# SPv0.net
KiCad netlist of a schematic drawn in EAGLE
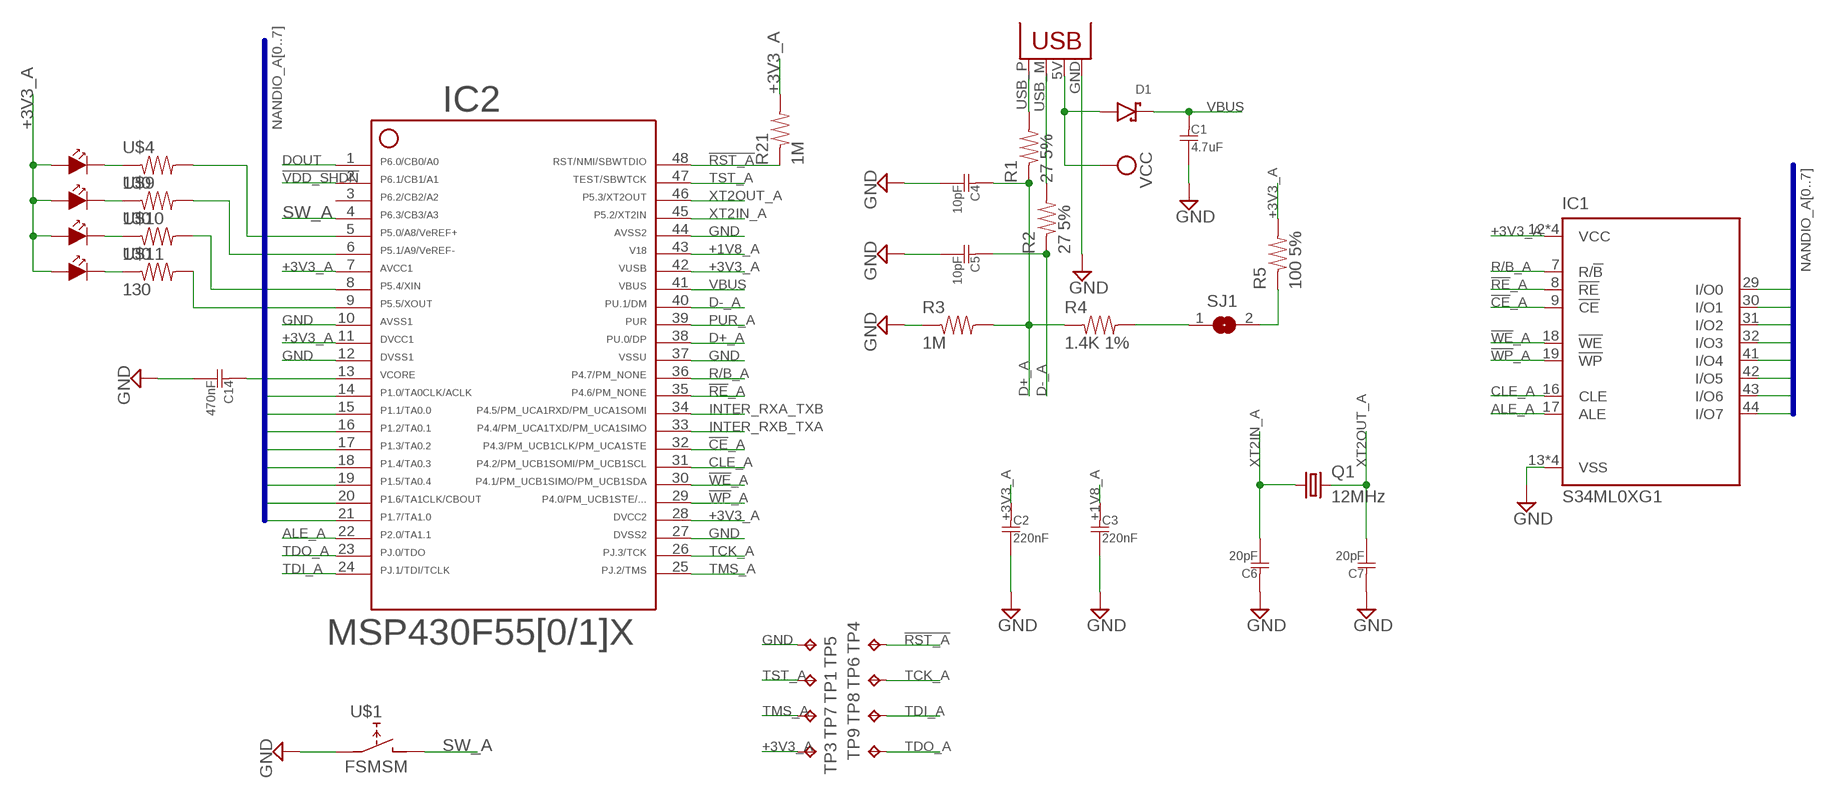
[diagram p0: schematic, sheet 1]
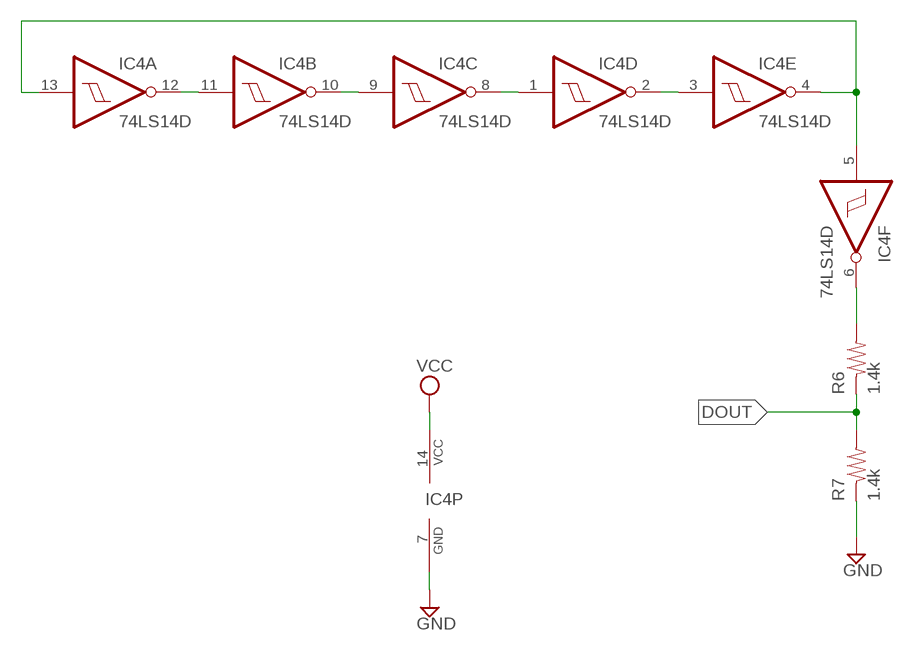
[diagram p1: schematic, sheet 2]

(export (version "E")
  (design (tool "Eeschema 10.0.6"))
  (components
    (comp (ref "IC4")
      (value "74LS14D")
      (footprint "eagle-import:SO14")
      (libsource (lib "eagle-import") (part "7414DLS"))
    )
    (comp (ref "R6")
      (value "1.4k")
      (footprint "eagle-import:R0805")
      (libsource (lib "eagle-import") (part "R0805"))
    )
    (comp (ref "R7")
      (value "1.4k")
      (footprint "eagle-import:R0805")
      (libsource (lib "eagle-import") (part "R0805"))
    )
    (comp (ref "C1")
      (value "4.7uF")
      (footprint "eagle-import:R0805")
      (libsource (lib "eagle-import") (part "C0805"))
    )
    (comp (ref "C2")
      (value "220nF")
      (footprint "eagle-import:R0805")
      (libsource (lib "eagle-import") (part "C0805"))
    )
    (comp (ref "C3")
      (value "220nF")
      (footprint "eagle-import:R0805")
      (libsource (lib "eagle-import") (part "C0805"))
    )
    (comp (ref "C4")
      (value "10pF")
      (footprint "eagle-import:R0805")
      (libsource (lib "eagle-import") (part "C0805"))
    )
    (comp (ref "C5")
      (value "10pF")
      (footprint "eagle-import:R0805")
      (libsource (lib "eagle-import") (part "C0805"))
    )
    (comp (ref "C6")
      (value "20pF")
      (footprint "eagle-import:R0805")
      (libsource (lib "eagle-import") (part "C0805"))
    )
    (comp (ref "C7")
      (value "20pF")
      (footprint "eagle-import:R0805")
      (libsource (lib "eagle-import") (part "C0805"))
    )
    (comp (ref "C14")
      (value "470nF")
      (footprint "eagle-import:R0805")
      (libsource (lib "eagle-import") (part "C0805"))
    )
    (comp (ref "D1")
      (value "D-SCHOTTKY")
      (footprint "eagle-import:SOD123")
      (libsource (lib "eagle-import") (part "D-SCHOTTKY"))
    )
    (comp (ref "IC1")
      (value "S34ML0XG1")
      (footprint "eagle-import:TSOP48")
      (libsource (lib "eagle-import") (part "S34ML0XG1"))
    )
    (comp (ref "IC2")
      (value "F55[0/1]X---PT48")
      (footprint "eagle-import:PT48")
      (libsource (lib "eagle-import") (part "F55[0/1]X---PT48"))
    )
    (comp (ref "JP1")
      (value "USBPCB")
      (footprint "eagle-import:USB-A-PCB")
      (libsource (lib "eagle-import") (part "USBPCB"))
    )
    (comp (ref "Q1")
      (value "12MHz")
      (footprint "eagle-import:CSM-3X")
      (libsource (lib "eagle-import") (part "CRYSTALCSM-3X"))
    )
    (comp (ref "R1")
      (value "27 5%")
      (footprint "eagle-import:R0805")
      (libsource (lib "eagle-import") (part "R0805"))
    )
    (comp (ref "R2")
      (value "27 5%")
      (footprint "eagle-import:R0805")
      (libsource (lib "eagle-import") (part "R0805"))
    )
    (comp (ref "R3")
      (value "1M")
      (footprint "eagle-import:R0805")
      (libsource (lib "eagle-import") (part "R0805"))
    )
    (comp (ref "R4")
      (value "1.4K 1%")
      (footprint "eagle-import:R0805")
      (libsource (lib "eagle-import") (part "R0805"))
    )
    (comp (ref "R5")
      (value "100 5%")
      (footprint "eagle-import:R0805")
      (libsource (lib "eagle-import") (part "R0805"))
    )
    (comp (ref "R21")
      (value "1M")
      (footprint "eagle-import:R0805")
      (libsource (lib "eagle-import") (part "R0805"))
    )
    (comp (ref "SJ1")
      (value "SJW")
      (footprint "eagle-import:SJW")
      (libsource (lib "eagle-import") (part "SJW"))
    )
    (comp (ref "TP1")
      (value "TPTP08SQ")
      (footprint "eagle-import:TP08SQ")
      (libsource (lib "eagle-import") (part "TPTP08SQ"))
    )
    (comp (ref "TP3")
      (value "TPTP08SQ")
      (footprint "eagle-import:TP08SQ")
      (libsource (lib "eagle-import") (part "TPTP08SQ"))
    )
    (comp (ref "TP4")
      (value "TPTP08SQ")
      (footprint "eagle-import:TP08SQ")
      (libsource (lib "eagle-import") (part "TPTP08SQ"))
    )
    (comp (ref "TP5")
      (value "TPTP08SQ")
      (footprint "eagle-import:TP08SQ")
      (libsource (lib "eagle-import") (part "TPTP08SQ"))
    )
    (comp (ref "TP6")
      (value "TPTP08SQ")
      (footprint "eagle-import:TP08SQ")
      (libsource (lib "eagle-import") (part "TPTP08SQ"))
    )
    (comp (ref "TP7")
      (value "TPTP08SQ")
      (footprint "eagle-import:TP08SQ")
      (libsource (lib "eagle-import") (part "TPTP08SQ"))
    )
    (comp (ref "TP8")
      (value "TPTP08SQ")
      (footprint "eagle-import:TP08SQ")
      (libsource (lib "eagle-import") (part "TPTP08SQ"))
    )
    (comp (ref "TP9")
      (value "TPTP08SQ")
      (footprint "eagle-import:TP08SQ")
      (libsource (lib "eagle-import") (part "TPTP08SQ"))
    )
    (comp (ref "U$1")
      (value "FSMSM")
      (footprint "eagle-import:FSMSM")
      (libsource (lib "eagle-import") (part "FSMSM"))
    )
    (comp (ref "U$4")
      (value "130")
      (footprint "eagle-import:R0805")
      (libsource (lib "eagle-import") (part "R0805"))
    )
    (comp (ref "U$5")
      (value "LED")
      (footprint "eagle-import:LED0805")
      (libsource (lib "eagle-import") (part "LED"))
    )
    (comp (ref "U$6")
      (value "LED")
      (footprint "eagle-import:LED0805")
      (libsource (lib "eagle-import") (part "LED"))
    )
    (comp (ref "U$7")
      (value "LED")
      (footprint "eagle-import:LED0805")
      (libsource (lib "eagle-import") (part "LED"))
    )
    (comp (ref "U$8")
      (value "LED")
      (footprint "eagle-import:LED0805")
      (libsource (lib "eagle-import") (part "LED"))
    )
    (comp (ref "U$9")
      (value "130")
      (footprint "eagle-import:R0805")
      (libsource (lib "eagle-import") (part "R0805"))
    )
    (comp (ref "U$10")
      (value "130")
      (footprint "eagle-import:R0805")
      (libsource (lib "eagle-import") (part "R0805"))
    )
    (comp (ref "U$11")
      (value "130")
      (footprint "eagle-import:R0805")
      (libsource (lib "eagle-import") (part "R0805"))
    )
  )
  (nets
    (net (code "1") (name "+1V8_A") (class "Default")
      (node (ref "C3") (pin "P$1") (pinfunction "1_P$1") (pintype "passive"))
      (node (ref "IC2") (pin "43") (pinfunction "43_43") (pintype "power_in"))
    )
    (net (code "2") (name "+3V3_A") (class "Default")
      (node (ref "C2") (pin "P$1") (pinfunction "1_P$1") (pintype "passive"))
      (node (ref "IC1") (pin "12") (pinfunction "VCC_12") (pintype "power_in"))
      (node (ref "IC1") (pin "34") (pinfunction "VCC_34") (pintype "power_in"))
      (node (ref "IC1") (pin "37") (pinfunction "VCC_37") (pintype "power_in"))
      (node (ref "IC1") (pin "39") (pinfunction "VCC_39") (pintype "power_in"))
      (node (ref "IC2") (pin "11") (pinfunction "11_11") (pintype "power_in"))
      (node (ref "IC2") (pin "28") (pinfunction "28_28") (pintype "power_in"))
      (node (ref "IC2") (pin "42") (pinfunction "42_42") (pintype "power_in"))
      (node (ref "IC2") (pin "7") (pinfunction "7_7") (pintype "power_in"))
      (node (ref "R21") (pin "P$2") (pinfunction "2_P$2") (pintype "passive"))
      (node (ref "R5") (pin "P$2") (pinfunction "2_P$2") (pintype "passive"))
      (node (ref "TP3") (pin "TP") (pinfunction "TP_TP") (pintype "input"))
      (node (ref "U$5") (pin "ANODE") (pinfunction "ANODE_ANODE") (pintype "passive"))
      (node (ref "U$6") (pin "ANODE") (pinfunction "ANODE_ANODE") (pintype "passive"))
      (node (ref "U$7") (pin "ANODE") (pinfunction "ANODE_ANODE") (pintype "passive"))
      (node (ref "U$8") (pin "ANODE") (pinfunction "ANODE_ANODE") (pintype "passive"))
    )
    (net (code "4") (name "ALE_A") (class "Default")
      (node (ref "IC1") (pin "17") (pinfunction "ALE_17") (pintype "input"))
      (node (ref "IC2") (pin "22") (pinfunction "22_22") (pintype "bidirectional"))
    )
    (net (code "5") (name "CLE_A") (class "Default")
      (node (ref "IC1") (pin "16") (pinfunction "CLE_16") (pintype "input"))
      (node (ref "IC2") (pin "31") (pinfunction "31_31") (pintype "bidirectional"))
    )
    (net (code "6") (name "D+_A") (class "Default")
      (node (ref "C4") (pin "P$1") (pinfunction "1_P$1") (pintype "passive"))
      (node (ref "IC2") (pin "38") (pinfunction "38_38") (pintype "bidirectional"))
      (node (ref "R1") (pin "P$1") (pinfunction "1_P$1") (pintype "passive"))
      (node (ref "R3") (pin "P$2") (pinfunction "2_P$2") (pintype "passive"))
      (node (ref "R4") (pin "P$1") (pinfunction "1_P$1") (pintype "passive"))
    )
    (net (code "7") (name "D-_A") (class "Default")
      (node (ref "C5") (pin "P$1") (pinfunction "1_P$1") (pintype "passive"))
      (node (ref "IC2") (pin "40") (pinfunction "40_40") (pintype "bidirectional"))
      (node (ref "R2") (pin "P$1") (pinfunction "1_P$1") (pintype "passive"))
    )
    (net (code "8") (name "DOUT") (class "Default")
      (node (ref "IC2") (pin "1") (pinfunction "1_1") (pintype "bidirectional"))
      (node (ref "R6") (pin "P$1") (pinfunction "1_P$1") (pintype "passive"))
      (node (ref "R7") (pin "P$2") (pinfunction "2_P$2") (pintype "passive"))
    )
    (net (code "9") (name "GND") (class "Default")
      (node (ref "C1") (pin "P$2") (pinfunction "2_P$2") (pintype "passive"))
      (node (ref "C14") (pin "P$2") (pinfunction "2_P$2") (pintype "passive"))
      (node (ref "C2") (pin "P$2") (pinfunction "2_P$2") (pintype "passive"))
      (node (ref "C3") (pin "P$2") (pinfunction "2_P$2") (pintype "passive"))
      (node (ref "C4") (pin "P$2") (pinfunction "2_P$2") (pintype "passive"))
      (node (ref "C5") (pin "P$2") (pinfunction "2_P$2") (pintype "passive"))
      (node (ref "C6") (pin "P$1") (pinfunction "1_P$1") (pintype "passive"))
      (node (ref "C7") (pin "P$1") (pinfunction "1_P$1") (pintype "passive"))
      (node (ref "IC1") (pin "13") (pinfunction "VSS_13") (pintype "power_in"))
      (node (ref "IC1") (pin "25") (pinfunction "VSS_25") (pintype "power_in"))
      (node (ref "IC1") (pin "36") (pinfunction "VSS_36") (pintype "power_in"))
      (node (ref "IC1") (pin "48") (pinfunction "VSS_48") (pintype "power_in"))
      (node (ref "IC2") (pin "10") (pinfunction "10_10") (pintype "power_in"))
      (node (ref "IC2") (pin "12") (pinfunction "12_12") (pintype "power_in"))
      (node (ref "IC2") (pin "27") (pinfunction "27_27") (pintype "power_in"))
      (node (ref "IC2") (pin "37") (pinfunction "37_37") (pintype "power_in"))
      (node (ref "IC2") (pin "44") (pinfunction "44_44") (pintype "power_in"))
      (node (ref "IC4") (pin "7") (pinfunction "GND_7") (pintype "power_in"))
      (node (ref "JP1") (pin "GND") (pinfunction "GND_GND") (pintype "bidirectional"))
      (node (ref "R3") (pin "P$1") (pinfunction "1_P$1") (pintype "passive"))
      (node (ref "R7") (pin "P$1") (pinfunction "1_P$1") (pintype "passive"))
      (node (ref "TP5") (pin "TP") (pinfunction "TP_TP") (pintype "input"))
      (node (ref "U$1") (pin "P$1") (pinfunction "A1_P$1") (pintype "passive"))
    )
    (net (code "10") (name "INTER_RXA_TXB") (class "Default")
      (node (ref "IC2") (pin "34") (pinfunction "34_34") (pintype "bidirectional"))
    )
    (net (code "11") (name "INTER_RXB_TXA") (class "Default")
      (node (ref "IC2") (pin "33") (pinfunction "33_33") (pintype "bidirectional"))
    )
    (net (code "12") (name "NANDIO_A0") (class "Default")
      (node (ref "IC1") (pin "29") (pinfunction "I/O0_29") (pintype "bidirectional"))
      (node (ref "IC2") (pin "14") (pinfunction "14_14") (pintype "bidirectional"))
    )
    (net (code "13") (name "NANDIO_A1") (class "Default")
      (node (ref "IC1") (pin "30") (pinfunction "I/O1_30") (pintype "bidirectional"))
      (node (ref "IC2") (pin "15") (pinfunction "15_15") (pintype "bidirectional"))
    )
    (net (code "14") (name "NANDIO_A2") (class "Default")
      (node (ref "IC1") (pin "31") (pinfunction "I/O2_31") (pintype "bidirectional"))
      (node (ref "IC2") (pin "16") (pinfunction "16_16") (pintype "bidirectional"))
    )
    (net (code "15") (name "NANDIO_A3") (class "Default")
      (node (ref "IC1") (pin "32") (pinfunction "I/O3_32") (pintype "bidirectional"))
      (node (ref "IC2") (pin "17") (pinfunction "17_17") (pintype "bidirectional"))
    )
    (net (code "16") (name "NANDIO_A4") (class "Default")
      (node (ref "IC1") (pin "41") (pinfunction "I/O4_41") (pintype "bidirectional"))
      (node (ref "IC2") (pin "18") (pinfunction "18_18") (pintype "bidirectional"))
    )
    (net (code "17") (name "NANDIO_A5") (class "Default")
      (node (ref "IC1") (pin "42") (pinfunction "I/O5_42") (pintype "bidirectional"))
      (node (ref "IC2") (pin "19") (pinfunction "19_19") (pintype "bidirectional"))
    )
    (net (code "18") (name "NANDIO_A6") (class "Default")
      (node (ref "IC1") (pin "43") (pinfunction "I/O6_43") (pintype "bidirectional"))
      (node (ref "IC2") (pin "20") (pinfunction "20_20") (pintype "bidirectional"))
    )
    (net (code "19") (name "NANDIO_A7") (class "Default")
      (node (ref "IC1") (pin "44") (pinfunction "I/O7_44") (pintype "bidirectional"))
      (node (ref "IC2") (pin "21") (pinfunction "21_21") (pintype "bidirectional"))
    )
    (net (code "20") (name "Net-(C14-1)") (class "Default")
      (node (ref "C14") (pin "P$1") (pinfunction "1_P$1") (pintype "passive"))
      (node (ref "IC2") (pin "13") (pinfunction "13_13") (pintype "power_in"))
    )
    (net (code "21") (name "Net-(IC4A-I)") (class "Default")
      (node (ref "IC4") (pin "13") (pinfunction "I_13") (pintype "input"))
      (node (ref "IC4") (pin "4") (pinfunction "O_4") (pintype "output"))
      (node (ref "IC4") (pin "5") (pinfunction "I_5") (pintype "input"))
    )
    (net (code "22") (name "Net-(IC4A-O)") (class "Default")
      (node (ref "IC4") (pin "11") (pinfunction "I_11") (pintype "input"))
      (node (ref "IC4") (pin "12") (pinfunction "O_12") (pintype "output"))
    )
    (net (code "23") (name "Net-(IC4B-O)") (class "Default")
      (node (ref "IC4") (pin "10") (pinfunction "O_10") (pintype "output"))
      (node (ref "IC4") (pin "9") (pinfunction "I_9") (pintype "input"))
    )
    (net (code "24") (name "Net-(IC4C-O)") (class "Default")
      (node (ref "IC4") (pin "1") (pinfunction "I_1") (pintype "input"))
      (node (ref "IC4") (pin "8") (pinfunction "O_8") (pintype "output"))
    )
    (net (code "25") (name "Net-(IC4D-O)") (class "Default")
      (node (ref "IC4") (pin "2") (pinfunction "O_2") (pintype "output"))
      (node (ref "IC4") (pin "3") (pinfunction "I_3") (pintype "input"))
    )
    (net (code "26") (name "Net-(IC4F-O)") (class "Default")
      (node (ref "IC4") (pin "6") (pinfunction "O_6") (pintype "output"))
      (node (ref "R6") (pin "P$2") (pinfunction "2_P$2") (pintype "passive"))
    )
    (net (code "27") (name "Net-(JP1-D+)") (class "Default")
      (node (ref "JP1") (pin "USB_P") (pinfunction "D+_USB_P") (pintype "bidirectional"))
      (node (ref "R1") (pin "P$2") (pinfunction "2_P$2") (pintype "passive"))
    )
    (net (code "28") (name "Net-(JP1-D-)") (class "Default")
      (node (ref "JP1") (pin "USB_M") (pinfunction "D-_USB_M") (pintype "bidirectional"))
      (node (ref "R2") (pin "P$2") (pinfunction "2_P$2") (pintype "passive"))
    )
    (net (code "29") (name "Net-(R4-2)") (class "Default")
      (node (ref "R4") (pin "P$2") (pinfunction "2_P$2") (pintype "passive"))
      (node (ref "SJ1") (pin "1") (pinfunction "1_1") (pintype "passive"))
    )
    (net (code "30") (name "Net-(R5-1)") (class "Default")
      (node (ref "R5") (pin "P$1") (pinfunction "1_P$1") (pintype "passive"))
      (node (ref "SJ1") (pin "2") (pinfunction "2_2") (pintype "passive"))
    )
    (net (code "31") (name "Net-(U$4-1)") (class "Default")
      (node (ref "U$4") (pin "P$1") (pinfunction "1_P$1") (pintype "passive"))
      (node (ref "U$5") (pin "CATHODE") (pinfunction "CATHODE_CATHODE") (pintype "passive"))
    )
    (net (code "32") (name "Net-(U$4-2)") (class "Default")
      (node (ref "IC2") (pin "5") (pinfunction "5_5") (pintype "bidirectional"))
      (node (ref "U$4") (pin "P$2") (pinfunction "2_P$2") (pintype "passive"))
    )
    (net (code "33") (name "Net-(U$9-1)") (class "Default")
      (node (ref "U$6") (pin "CATHODE") (pinfunction "CATHODE_CATHODE") (pintype "passive"))
      (node (ref "U$9") (pin "P$1") (pinfunction "1_P$1") (pintype "passive"))
    )
    (net (code "34") (name "Net-(U$9-2)") (class "Default")
      (node (ref "IC2") (pin "6") (pinfunction "6_6") (pintype "bidirectional"))
      (node (ref "U$9") (pin "P$2") (pinfunction "2_P$2") (pintype "passive"))
    )
    (net (code "35") (name "Net-(U$10-1)") (class "Default")
      (node (ref "U$10") (pin "P$1") (pinfunction "1_P$1") (pintype "passive"))
      (node (ref "U$7") (pin "CATHODE") (pinfunction "CATHODE_CATHODE") (pintype "passive"))
    )
    (net (code "36") (name "Net-(U$10-2)") (class "Default")
      (node (ref "IC2") (pin "8") (pinfunction "8_8") (pintype "bidirectional"))
      (node (ref "U$10") (pin "P$2") (pinfunction "2_P$2") (pintype "passive"))
    )
    (net (code "37") (name "Net-(U$11-1)") (class "Default")
      (node (ref "U$11") (pin "P$1") (pinfunction "1_P$1") (pintype "passive"))
      (node (ref "U$8") (pin "CATHODE") (pinfunction "CATHODE_CATHODE") (pintype "passive"))
    )
    (net (code "38") (name "Net-(U$11-2)") (class "Default")
      (node (ref "IC2") (pin "9") (pinfunction "9_9") (pintype "bidirectional"))
      (node (ref "U$11") (pin "P$2") (pinfunction "2_P$2") (pintype "passive"))
    )
    (net (code "39") (name "PUR_A") (class "Default")
      (node (ref "IC2") (pin "39") (pinfunction "39_39") (pintype "bidirectional"))
    )
    (net (code "40") (name "R{slash}B_A") (class "Default")
      (node (ref "IC1") (pin "7") (pinfunction "R/~{B}_7") (pintype "input"))
      (node (ref "IC2") (pin "36") (pinfunction "36_36") (pintype "bidirectional"))
    )
    (net (code "41") (name "SW_A") (class "Default")
      (node (ref "IC2") (pin "4") (pinfunction "4_4") (pintype "bidirectional"))
      (node (ref "U$1") (pin "P$2") (pinfunction "B_P$2") (pintype "passive"))
    )
    (net (code "42") (name "TCK_A") (class "Default")
      (node (ref "IC2") (pin "26") (pinfunction "26_26") (pintype "bidirectional"))
      (node (ref "TP6") (pin "TP") (pinfunction "TP_TP") (pintype "input"))
    )
    (net (code "43") (name "TDI_A") (class "Default")
      (node (ref "IC2") (pin "24") (pinfunction "24_24") (pintype "bidirectional"))
      (node (ref "TP8") (pin "TP") (pinfunction "TP_TP") (pintype "input"))
    )
    (net (code "44") (name "TDO_A") (class "Default")
      (node (ref "IC2") (pin "23") (pinfunction "23_23") (pintype "bidirectional"))
      (node (ref "TP9") (pin "TP") (pinfunction "TP_TP") (pintype "input"))
    )
    (net (code "45") (name "TMS_A") (class "Default")
      (node (ref "IC2") (pin "25") (pinfunction "25_25") (pintype "bidirectional"))
      (node (ref "TP7") (pin "TP") (pinfunction "TP_TP") (pintype "input"))
    )
    (net (code "46") (name "TST_A") (class "Default")
      (node (ref "IC2") (pin "47") (pinfunction "47_47") (pintype "input"))
      (node (ref "TP1") (pin "TP") (pinfunction "TP_TP") (pintype "input"))
    )
    (net (code "47") (name "VBUS") (class "Default")
      (node (ref "C1") (pin "P$1") (pinfunction "1_P$1") (pintype "passive"))
      (node (ref "D1") (pin "CATHODE") (pinfunction "CATHODE_CATHODE") (pintype "passive"))
      (node (ref "IC2") (pin "41") (pinfunction "41_41") (pintype "power_in"))
    )
    (net (code "48") (name "VCC") (class "Default")
      (node (ref "D1") (pin "ANODE") (pinfunction "ANODE_ANODE") (pintype "passive"))
      (node (ref "IC4") (pin "14") (pinfunction "VCC_14") (pintype "power_in"))
      (node (ref "JP1") (pin "5V") (pinfunction "VBUS_5V") (pintype "bidirectional"))
    )
    (net (code "49") (name "XT2IN_A") (class "Default")
      (node (ref "C6") (pin "P$2") (pinfunction "2_P$2") (pintype "passive"))
      (node (ref "IC2") (pin "45") (pinfunction "45_45") (pintype "bidirectional"))
      (node (ref "Q1") (pin "P$1") (pinfunction "1_P$1") (pintype "passive"))
    )
    (net (code "50") (name "XT2OUT_A") (class "Default")
      (node (ref "C7") (pin "P$2") (pinfunction "2_P$2") (pintype "passive"))
      (node (ref "IC2") (pin "46") (pinfunction "46_46") (pintype "power_in"))
      (node (ref "Q1") (pin "P$2") (pinfunction "2_P$2") (pintype "passive"))
    )
    (net (code "51") (name "unconnected-(IC2-Pad3)") (class "Default")
      (node (ref "IC2") (pin "3") (pinfunction "3_3") (pintype "bidirectional"))
    )
    (net (code "52") (name "~{CE}_A") (class "Default")
      (node (ref "IC1") (pin "9") (pinfunction "~{CE}_9") (pintype "input"))
      (node (ref "IC2") (pin "32") (pinfunction "32_32") (pintype "bidirectional"))
    )
    (net (code "53") (name "~{RE}_A") (class "Default")
      (node (ref "IC1") (pin "8") (pinfunction "~{RE}_8") (pintype "input"))
      (node (ref "IC2") (pin "35") (pinfunction "35_35") (pintype "bidirectional"))
    )
    (net (code "54") (name "~{RST_A}") (class "Default")
      (node (ref "IC2") (pin "48") (pinfunction "48_48") (pintype "bidirectional"))
      (node (ref "R21") (pin "P$1") (pinfunction "1_P$1") (pintype "passive"))
      (node (ref "TP4") (pin "TP") (pinfunction "TP_TP") (pintype "input"))
    )
    (net (code "55") (name "~{VDD_SHDN}") (class "Default")
      (node (ref "IC2") (pin "2") (pinfunction "2_2") (pintype "bidirectional"))
    )
    (net (code "56") (name "~{WE}_A") (class "Default")
      (node (ref "IC1") (pin "18") (pinfunction "~{WE}_18") (pintype "input"))
      (node (ref "IC2") (pin "30") (pinfunction "30_30") (pintype "bidirectional"))
    )
    (net (code "57") (name "~{WP}_A") (class "Default")
      (node (ref "IC1") (pin "19") (pinfunction "~{WP}_19") (pintype "input"))
      (node (ref "IC2") (pin "29") (pinfunction "29_29") (pintype "bidirectional"))
    )
  )
)
